# Precharge.net
KiCad netlist of a schematic drawn in Altium Designer
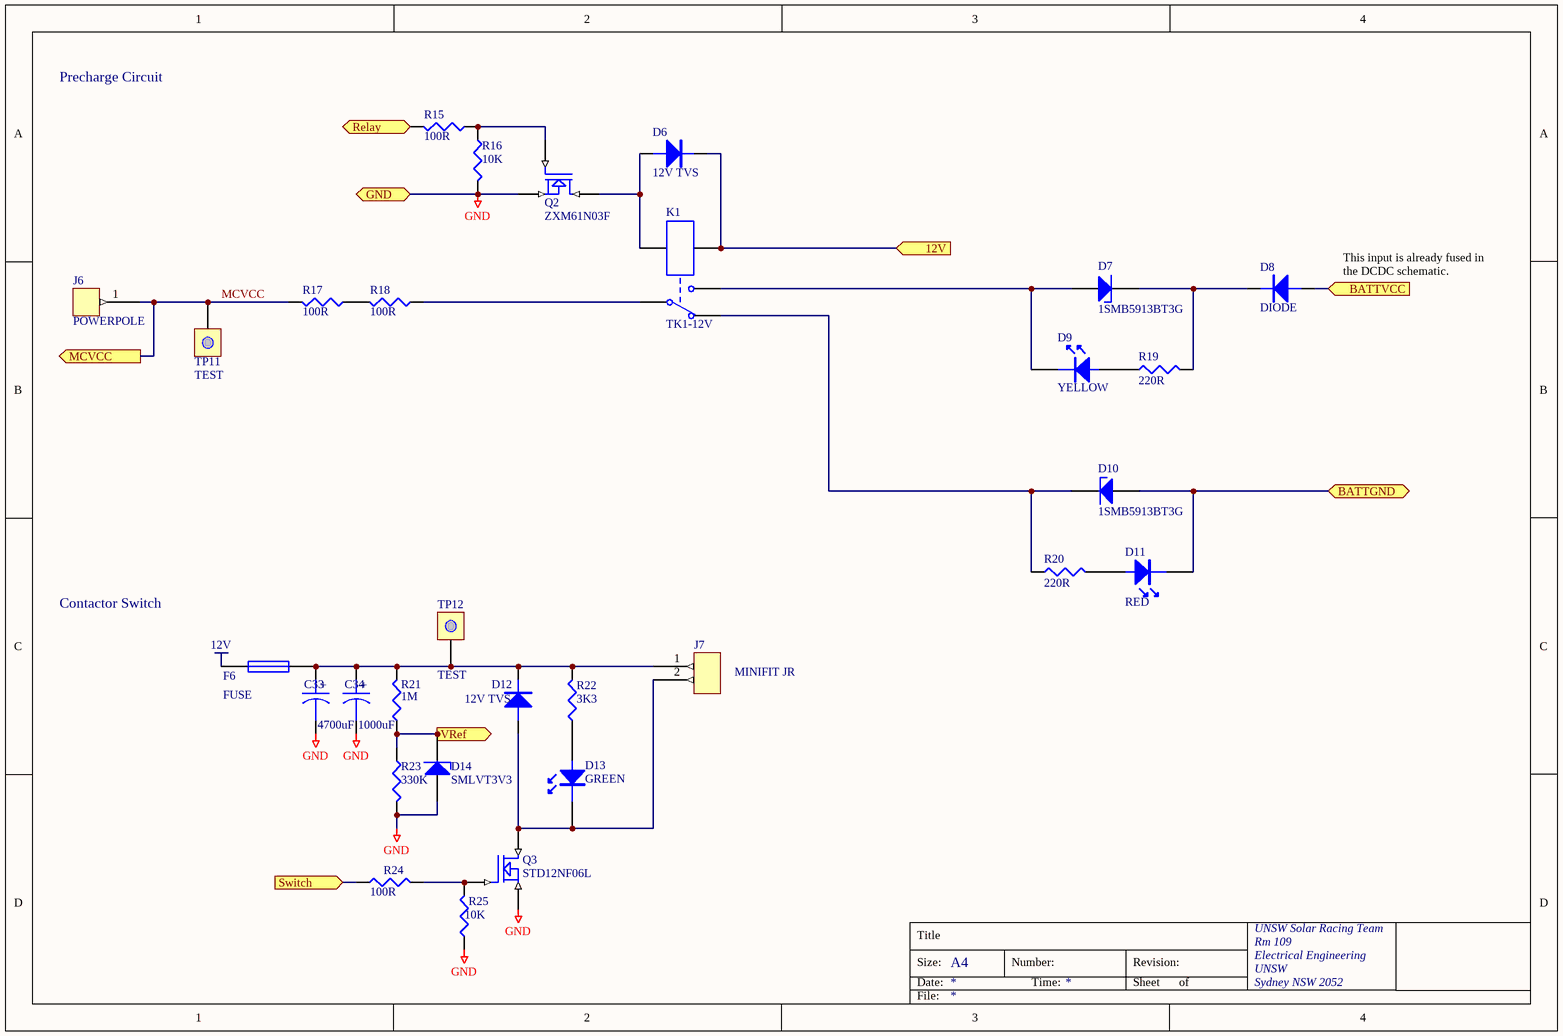
[diagram p0: Precharge.SCHDOC]

(export (version "E")
  (design (tool "Eeschema 10.0.6"))
  (components
    (comp (ref "C33")
      (value "4700uF")
      (footprint "ELECTROLYTIC-10-20")
      (description "Capacitor")
      (libsource (lib "*") (part "CAPACITOR POL"))
    )
    (comp (ref "C34")
      (value "1000uF")
      (footprint "ELECTROLYTIC-5-10")
      (description "Capacitor")
      (libsource (lib "*") (part "CAPACITOR POL"))
    )
    (comp (ref "D6")
      (value "12V TVS")
      (footprint "SMA")
      (description "Diode")
      (libsource (lib "RCLDQ") (part "DIODE"))
    )
    (comp (ref "D7")
      (value "1SMB5913BT3G")
      (footprint "Footprint:SMB")
      (description "Zener Diode")
      (libsource (lib "RCLDQ") (part "ZENER1"))
    )
    (comp (ref "D8")
      (value "DIODE")
      (footprint "DIODE-D1.2mm")
      (description "Diode")
      (libsource (lib "RCLDQ") (part "DIODE"))
    )
    (comp (ref "D9") (value "YELLOW") (footprint "LED-RA") (libsource (lib "*") (part "LED")))
    (comp (ref "D10")
      (value "1SMB5913BT3G")
      (footprint "Footprint:SMB")
      (description "Zener Diode")
      (libsource (lib "RCLDQ") (part "ZENER1"))
    )
    (comp (ref "D11") (value "RED") (footprint "LED-RA") (libsource (lib "*") (part "LED")))
    (comp (ref "D12")
      (value "12V TVS")
      (footprint "SMA")
      (description "Diode")
      (libsource (lib "RCLDQ") (part "DIODE"))
    )
    (comp (ref "D13") (value "GREEN") (footprint "LED-RA") (libsource (lib "") (part "LED_1")))
    (comp (ref "D14")
      (value "SMLVT3V3")
      (footprint "SMB")
      (description "TVS")
      (libsource (lib "RCLDQ") (part "ZENER1"))
    )
    (comp (ref "F6")
      (value "FUSE")
      (footprint "LITTELFUSE-154")
      (description "Fuse")
      (libsource (lib "Miscellaneous") (part "FUSE"))
    )
    (comp (ref "J6")
      (value "POWERPOLE")
      (footprint "POWERPOLE25A")
      (libsource (lib "Connectors") (part "CON1"))
    )
    (comp (ref "J7")
      (value "MINIFIT JR")
      (footprint "MINIFITJR-2")
      (libsource (lib "Connectors") (part "CON2"))
    )
    (comp (ref "K1")
      (value "TK1-12V")
      (footprint "TK1-12V")
      (description "SPCO 12V 2A Relay")
      (libsource (lib "RCLDQ") (part "TK1-12V"))
    )
    (comp (ref "Q2")
      (value "ZXM61N03F")
      (footprint "SOT23-3")
      (description "1.7A, 20V N-Channel Enhancement mode FET")
      (libsource (lib "RCLDQ") (part "ZXM61N02F"))
    )
    (comp (ref "Q3")
      (value "STD12NF06L")
      (footprint "DPAK_N-MOSFET")
      (description "N-type MOSFET")
      (libsource (lib "RCLDQ") (part "STD12NF06L"))
    )
    (comp (ref "R15") (value "100R") (footprint "0603") (libsource (lib "*") (part "RES1")))
    (comp (ref "R16")
      (value "10K")
      (footprint "0603")
      (description "Resistor")
      (libsource (lib "*") (part "RES1"))
    )
    (comp (ref "R17")
      (value "100R")
      (footprint "LTO100")
      (description "Resistor")
      (libsource (lib "RCLDQ") (part "RES1"))
    )
    (comp (ref "R18")
      (value "100R")
      (footprint "LTO100")
      (description "Resistor")
      (libsource (lib "RCLDQ") (part "RES1"))
    )
    (comp (ref "R19")
      (value "220R")
      (footprint "0805")
      (description "Resistor")
      (libsource (lib "RCLDQ") (part "RES1"))
    )
    (comp (ref "R20")
      (value "220R")
      (footprint "0805")
      (description "Resistor")
      (libsource (lib "RCLDQ") (part "RES1"))
    )
    (comp (ref "R21") (value "1M") (footprint "0603") (libsource (lib "RCLDQ") (part "RES1")))
    (comp (ref "R22") (value "3K3") (footprint "0603") (libsource (lib "RCLDQ") (part "RES1")))
    (comp (ref "R23") (value "330K") (footprint "0603") (libsource (lib "RCLDQ") (part "RES1")))
    (comp (ref "R24") (value "100R") (footprint "0603") (libsource (lib "RCLDQ") (part "RES1")))
    (comp (ref "R25")
      (value "10K")
      (footprint "0603")
      (description "Resistor")
      (libsource (lib "*") (part "RES1"))
    )
    (comp (ref "TP11")
      (value "TEST")
      (footprint "TESTPOINT")
      (description "TEST POINT")
      (libsource (lib "") (part "TEST_1"))
    )
    (comp (ref "TP12")
      (value "TEST")
      (footprint "TESTPOINT")
      (description "TEST POINT")
      (libsource (lib "Miscellaneous") (part "TEST"))
    )
  )
  (nets
    (net (code "1") (name "/BATTGND") (class "Default")
      (node (ref "D10") (pin "A") (pinfunction "A_A") (pintype "passive"))
      (node (ref "D11") (pin "K") (pinfunction "2_K") (pintype "passive"))
    )
    (net (code "2") (name "/BATTVCC") (class "Default")
      (node (ref "D8") (pin "A") (pinfunction "A_A") (pintype "passive"))
    )
    (net (code "3") (name "/MCVCC") (class "Default")
      (node (ref "J6") (pin "1") (pinfunction "1_1") (pintype "output"))
      (node (ref "R17") (pin "2") (pinfunction "2_2") (pintype "passive"))
      (node (ref "TP11") (pin "0") (pinfunction "TP_0") (pintype "passive"))
    )
    (net (code "4") (name "/Relay") (class "Default")
      (node (ref "R15") (pin "2") (pinfunction "2_2") (pintype "passive"))
    )
    (net (code "5") (name "/Switch") (class "Default")
      (node (ref "R24") (pin "1") (pinfunction "1_1") (pintype "passive"))
    )
    (net (code "6") (name "/VRef") (class "Default")
      (node (ref "D14") (pin "K") (pinfunction "K_K") (pintype "passive"))
      (node (ref "R21") (pin "1") (pinfunction "1_1") (pintype "passive"))
      (node (ref "R23") (pin "1") (pinfunction "1_1") (pintype "passive"))
    )
    (net (code "7") (name "12V") (class "Default")
      (node (ref "D6") (pin "K") (pinfunction "K_K") (pintype "passive"))
      (node (ref "F6") (pin "1") (pinfunction "1_1") (pintype "passive"))
      (node (ref "K1") (pin "1") (pinfunction "1_1") (pintype "passive"))
    )
    (net (code "8") (name "GND") (class "Default")
      (node (ref "C33") (pin "2") (pinfunction "2_2") (pintype "passive"))
      (node (ref "C34") (pin "2") (pinfunction "2_2") (pintype "passive"))
      (node (ref "D14") (pin "A") (pinfunction "A_A") (pintype "passive"))
      (node (ref "Q2") (pin "2") (pinfunction "S_2") (pintype "input"))
      (node (ref "Q3") (pin "3") (pinfunction "S_3") (pintype "input"))
      (node (ref "R16") (pin "2") (pinfunction "2_2") (pintype "passive"))
      (node (ref "R23") (pin "2") (pinfunction "2_2") (pintype "passive"))
      (node (ref "R25") (pin "1") (pinfunction "1_1") (pintype "passive"))
    )
    (net (code "9") (name "Net-(D7-PadK)") (class "Default")
      (node (ref "D7") (pin "K") (pinfunction "K_K") (pintype "passive"))
      (node (ref "D8") (pin "K") (pinfunction "K_K") (pintype "passive"))
      (node (ref "R19") (pin "2") (pinfunction "2_2") (pintype "passive"))
    )
    (net (code "10") (name "Net-(D9-1)") (class "Default")
      (node (ref "D9") (pin "A") (pinfunction "1_A") (pintype "passive"))
      (node (ref "R19") (pin "1") (pinfunction "1_1") (pintype "passive"))
    )
    (net (code "11") (name "Net-(D9-2)") (class "Default")
      (node (ref "D7") (pin "A") (pinfunction "A_A") (pintype "passive"))
      (node (ref "D9") (pin "K") (pinfunction "2_K") (pintype "passive"))
      (node (ref "K1") (pin "6") (pinfunction "6_6") (pintype "passive"))
    )
    (net (code "12") (name "Net-(D10-PadK)") (class "Default")
      (node (ref "D10") (pin "K") (pinfunction "K_K") (pintype "passive"))
      (node (ref "K1") (pin "4") (pinfunction "4_4") (pintype "passive"))
      (node (ref "R20") (pin "1") (pinfunction "1_1") (pintype "passive"))
    )
    (net (code "13") (name "Net-(D11-1)") (class "Default")
      (node (ref "D11") (pin "A") (pinfunction "1_A") (pintype "passive"))
      (node (ref "R20") (pin "2") (pinfunction "2_2") (pintype "passive"))
    )
    (net (code "14") (name "Net-(D13-1)") (class "Default")
      (node (ref "D13") (pin "A") (pinfunction "1_A") (pintype "passive"))
      (node (ref "R22") (pin "1") (pinfunction "1_1") (pintype "passive"))
    )
    (net (code "15") (name "Net-(D13-2)") (class "Default")
      (node (ref "D12") (pin "A") (pinfunction "A_A") (pintype "passive"))
      (node (ref "D13") (pin "K") (pinfunction "2_K") (pintype "passive"))
      (node (ref "J7") (pin "2") (pinfunction "2_2") (pintype "output"))
      (node (ref "Q3") (pin "2") (pinfunction "D_2") (pintype "input"))
    )
    (net (code "16") (name "Net-(K1-Pad5)") (class "Default")
      (node (ref "K1") (pin "5") (pinfunction "5_5") (pintype "passive"))
      (node (ref "R18") (pin "1") (pinfunction "1_1") (pintype "passive"))
    )
    (net (code "17") (name "Net-(Q2-D)") (class "Default")
      (node (ref "D6") (pin "A") (pinfunction "A_A") (pintype "passive"))
      (node (ref "K1") (pin "3") (pinfunction "3_3") (pintype "passive"))
      (node (ref "Q2") (pin "3") (pinfunction "D_3") (pintype "input"))
    )
    (net (code "18") (name "Net-(Q2-G)") (class "Default")
      (node (ref "Q2") (pin "1") (pinfunction "G_1") (pintype "input"))
      (node (ref "R15") (pin "1") (pinfunction "1_1") (pintype "passive"))
      (node (ref "R16") (pin "1") (pinfunction "1_1") (pintype "passive"))
    )
    (net (code "19") (name "Net-(Q3-G)") (class "Default")
      (node (ref "Q3") (pin "1") (pinfunction "G_1") (pintype "input"))
      (node (ref "R24") (pin "2") (pinfunction "2_2") (pintype "passive"))
      (node (ref "R25") (pin "2") (pinfunction "2_2") (pintype "passive"))
    )
    (net (code "20") (name "Net-(R17-Pad1)") (class "Default")
      (node (ref "R17") (pin "1") (pinfunction "1_1") (pintype "passive"))
      (node (ref "R18") (pin "2") (pinfunction "2_2") (pintype "passive"))
    )
    (net (code "21") (name "Net-(TP12-TP)") (class "Default")
      (node (ref "C33") (pin "1") (pinfunction "1_1") (pintype "passive"))
      (node (ref "C34") (pin "1") (pinfunction "1_1") (pintype "passive"))
      (node (ref "D12") (pin "K") (pinfunction "K_K") (pintype "passive"))
      (node (ref "F6") (pin "2") (pinfunction "2_2") (pintype "passive"))
      (node (ref "J7") (pin "1") (pinfunction "1_1") (pintype "output"))
      (node (ref "R21") (pin "2") (pinfunction "2_2") (pintype "passive"))
      (node (ref "R22") (pin "2") (pinfunction "2_2") (pintype "passive"))
      (node (ref "TP12") (pin "0") (pinfunction "TP_0") (pintype "passive"))
    )
  )
)
